# drone_V2.net
KiCad netlist of a schematic drawn in EAGLE
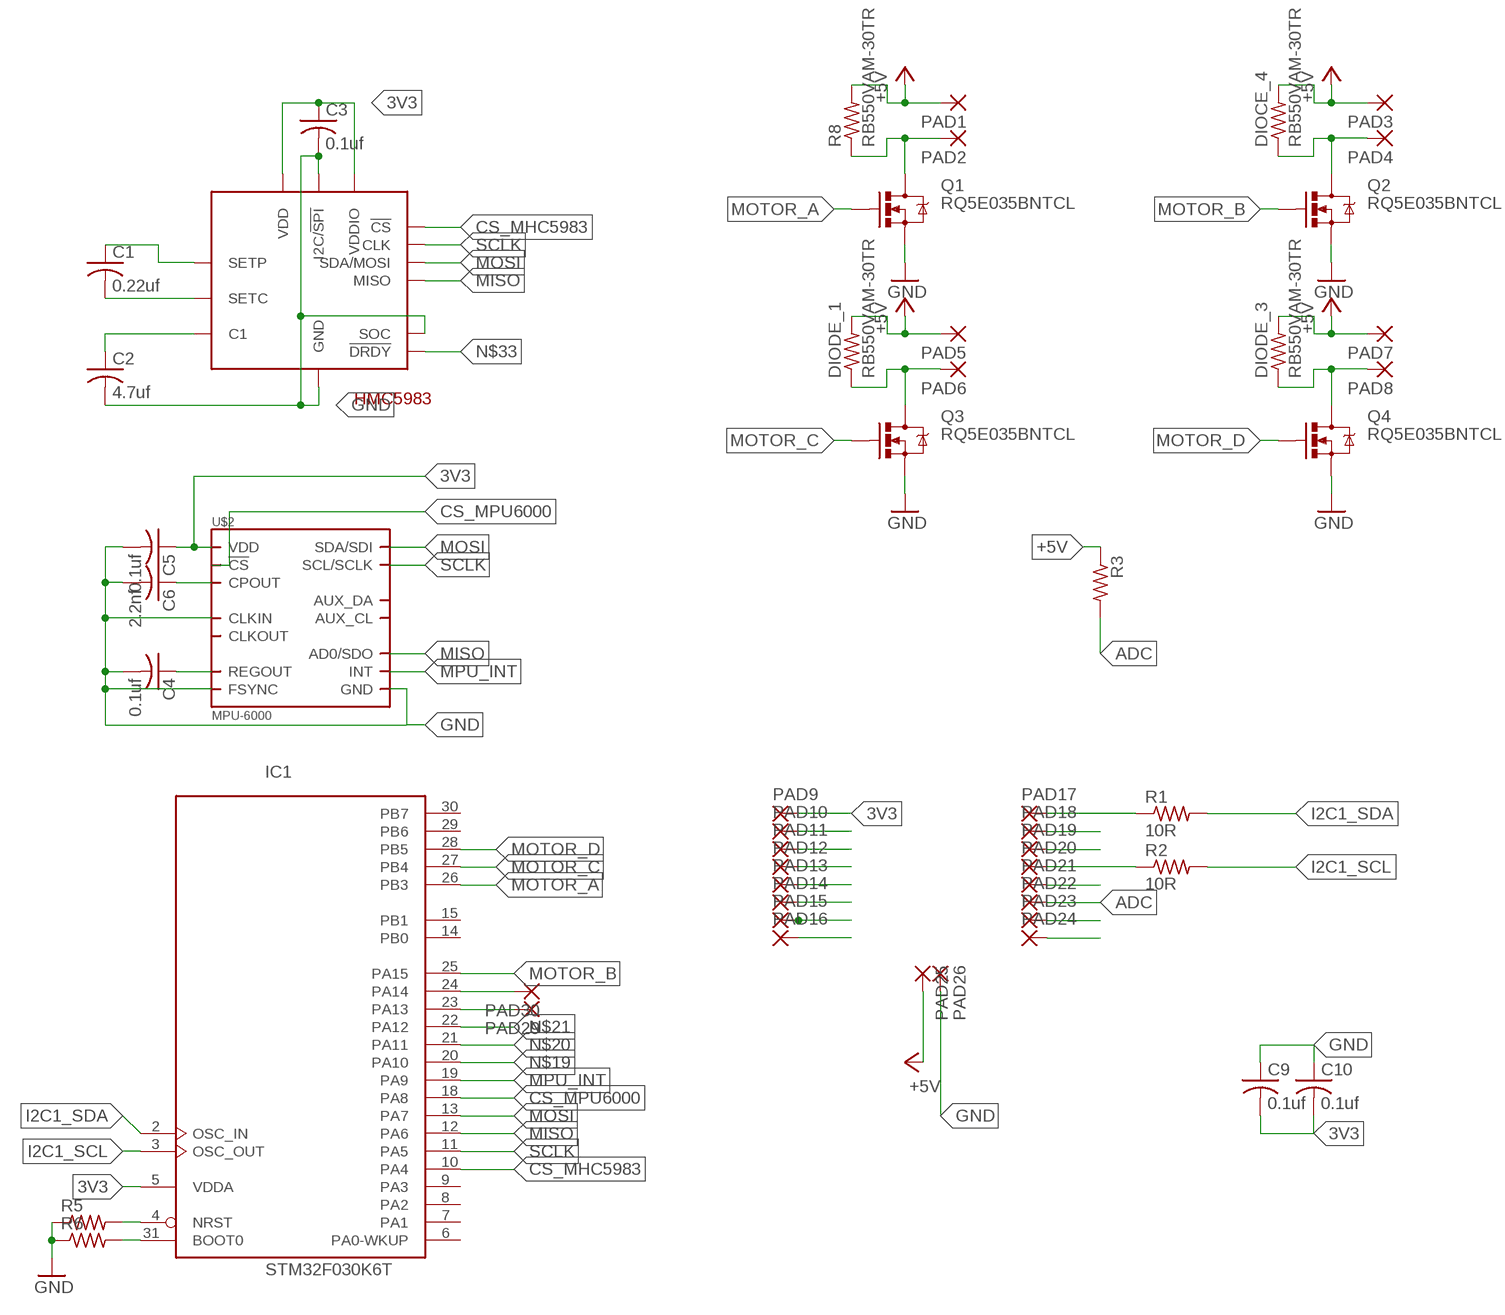
[diagram p0: schematic, sheet 1]

(export (version "E")
  (design (tool "Eeschema 10.0.6"))
  (components
    (comp (ref "C1")
      (value "0.22uf")
      (footprint "eagle-import:C0805K")
      (libsource (lib "eagle-import") (part "C-USC0805K"))
    )
    (comp (ref "C2")
      (value "4.7uf")
      (footprint "eagle-import:C1206")
      (libsource (lib "eagle-import") (part "C-USC1206"))
    )
    (comp (ref "C3")
      (value "0.1uf")
      (footprint "eagle-import:C0805K")
      (libsource (lib "eagle-import") (part "C-USC0805K"))
    )
    (comp (ref "C4")
      (value "0.1uf")
      (footprint "eagle-import:C0805K")
      (libsource (lib "eagle-import") (part "C-USC0805K"))
    )
    (comp (ref "C5")
      (value "0.1uf")
      (footprint "eagle-import:C0805K")
      (libsource (lib "eagle-import") (part "C-USC0805K"))
    )
    (comp (ref "C6")
      (value "2.2nf")
      (footprint "eagle-import:C0805K")
      (libsource (lib "eagle-import") (part "C-USC0805K"))
    )
    (comp (ref "C9")
      (value "0.1uf")
      (footprint "eagle-import:C0805K")
      (libsource (lib "eagle-import") (part "C-USC0805K"))
    )
    (comp (ref "C10")
      (value "0.1uf")
      (footprint "eagle-import:C0805K")
      (libsource (lib "eagle-import") (part "C-USC0805K"))
    )
    (comp (ref "DIOCE_4")
      (value "RB550VAM-30TR")
      (footprint "eagle-import:R0805")
      (libsource (lib "eagle-import") (part "R-US_R0805"))
    )
    (comp (ref "DIODE_1")
      (value "RB550VAM-30TR")
      (footprint "eagle-import:R0805")
      (libsource (lib "eagle-import") (part "R-US_R0805"))
    )
    (comp (ref "DIODE_3")
      (value "RB550VAM-30TR")
      (footprint "eagle-import:R0805")
      (libsource (lib "eagle-import") (part "R-US_R0805"))
    )
    (comp (ref "HMC5983")
      (value "HMC5983")
      (footprint "eagle-import:LPCC16")
      (libsource (lib "eagle-import") (part "HMC5983"))
    )
    (comp (ref "IC1")
      (value "STM32F030K6T")
      (footprint "eagle-import:LQFP32")
      (libsource (lib "eagle-import") (part "STM32F030KT6"))
    )
    (comp (ref "PAD1")
      (value "1,6/0,8")
      (footprint "eagle-import:1,6_0,8")
      (libsource (lib "eagle-import") (part "1,6/0,8"))
    )
    (comp (ref "PAD2")
      (value "1,6/0,8")
      (footprint "eagle-import:1,6_0,8")
      (libsource (lib "eagle-import") (part "1,6/0,8"))
    )
    (comp (ref "PAD3")
      (value "1,6/0,8")
      (footprint "eagle-import:1,6_0,8")
      (libsource (lib "eagle-import") (part "1,6/0,8"))
    )
    (comp (ref "PAD4")
      (value "1,6/0,8")
      (footprint "eagle-import:1,6_0,8")
      (libsource (lib "eagle-import") (part "1,6/0,8"))
    )
    (comp (ref "PAD5")
      (value "1,6/0,8")
      (footprint "eagle-import:1,6_0,8")
      (libsource (lib "eagle-import") (part "1,6/0,8"))
    )
    (comp (ref "PAD6")
      (value "1,6/0,8")
      (footprint "eagle-import:1,6_0,8")
      (libsource (lib "eagle-import") (part "1,6/0,8"))
    )
    (comp (ref "PAD7")
      (value "1,6/0,8")
      (footprint "eagle-import:1,6_0,8")
      (libsource (lib "eagle-import") (part "1,6/0,8"))
    )
    (comp (ref "PAD8")
      (value "1,6/0,8")
      (footprint "eagle-import:1,6_0,8")
      (libsource (lib "eagle-import") (part "1,6/0,8"))
    )
    (comp (ref "PAD9")
      (value "1,6/0,9")
      (footprint "eagle-import:1,6_0,9")
      (libsource (lib "eagle-import") (part "1,6/0,9"))
    )
    (comp (ref "PAD10")
      (value "1,6/0,9")
      (footprint "eagle-import:1,6_0,9")
      (libsource (lib "eagle-import") (part "1,6/0,9"))
    )
    (comp (ref "PAD11")
      (value "1,6/0,9")
      (footprint "eagle-import:1,6_0,9")
      (libsource (lib "eagle-import") (part "1,6/0,9"))
    )
    (comp (ref "PAD12")
      (value "1,6/0,9")
      (footprint "eagle-import:1,6_0,9")
      (libsource (lib "eagle-import") (part "1,6/0,9"))
    )
    (comp (ref "PAD13")
      (value "1,6/0,9")
      (footprint "eagle-import:1,6_0,9")
      (libsource (lib "eagle-import") (part "1,6/0,9"))
    )
    (comp (ref "PAD14")
      (value "1,6/0,9")
      (footprint "eagle-import:1,6_0,9")
      (libsource (lib "eagle-import") (part "1,6/0,9"))
    )
    (comp (ref "PAD15")
      (value "1,6/0,9")
      (footprint "eagle-import:1,6_0,9")
      (libsource (lib "eagle-import") (part "1,6/0,9"))
    )
    (comp (ref "PAD16")
      (value "1,6/0,9")
      (footprint "eagle-import:1,6_0,9")
      (libsource (lib "eagle-import") (part "1,6/0,9"))
    )
    (comp (ref "PAD17")
      (value "1,6/0,9")
      (footprint "eagle-import:1,6_0,9")
      (libsource (lib "eagle-import") (part "1,6/0,9"))
    )
    (comp (ref "PAD18")
      (value "1,6/0,9")
      (footprint "eagle-import:1,6_0,9")
      (libsource (lib "eagle-import") (part "1,6/0,9"))
    )
    (comp (ref "PAD19")
      (value "1,6/0,9")
      (footprint "eagle-import:1,6_0,9")
      (libsource (lib "eagle-import") (part "1,6/0,9"))
    )
    (comp (ref "PAD20")
      (value "1,6/0,9")
      (footprint "eagle-import:1,6_0,9")
      (libsource (lib "eagle-import") (part "1,6/0,9"))
    )
    (comp (ref "PAD21")
      (value "1,6/0,9")
      (footprint "eagle-import:1,6_0,9")
      (libsource (lib "eagle-import") (part "1,6/0,9"))
    )
    (comp (ref "PAD22")
      (value "1,6/0,9")
      (footprint "eagle-import:1,6_0,9")
      (libsource (lib "eagle-import") (part "1,6/0,9"))
    )
    (comp (ref "PAD23")
      (value "1,6/0,9")
      (footprint "eagle-import:1,6_0,9")
      (libsource (lib "eagle-import") (part "1,6/0,9"))
    )
    (comp (ref "PAD24")
      (value "1,6/0,9")
      (footprint "eagle-import:1,6_0,9")
      (libsource (lib "eagle-import") (part "1,6/0,9"))
    )
    (comp (ref "PAD25")
      (value "1,6/0,9")
      (footprint "eagle-import:1,6_0,9")
      (libsource (lib "eagle-import") (part "1,6/0,9"))
    )
    (comp (ref "PAD26")
      (value "1,6/0,9")
      (footprint "eagle-import:1,6_0,9")
      (libsource (lib "eagle-import") (part "1,6/0,9"))
    )
    (comp (ref "PAD29")
      (value "1,6/0,9")
      (footprint "eagle-import:1,6_0,9")
      (libsource (lib "eagle-import") (part "1,6/0,9"))
    )
    (comp (ref "PAD30")
      (value "1,6/0,9")
      (footprint "eagle-import:1,6_0,9")
      (libsource (lib "eagle-import") (part "1,6/0,9"))
    )
    (comp (ref "Q1")
      (value "RQ5E035BNTCL")
      (footprint "eagle-import:SOT23-3")
      (libsource (lib "eagle-import") (part "MOSFET-NCHANNELSMD"))
    )
    (comp (ref "Q2")
      (value "RQ5E035BNTCL")
      (footprint "eagle-import:SOT23-3")
      (libsource (lib "eagle-import") (part "MOSFET-NCHANNELSMD"))
    )
    (comp (ref "Q3")
      (value "RQ5E035BNTCL")
      (footprint "eagle-import:SOT23-3")
      (libsource (lib "eagle-import") (part "MOSFET-NCHANNELSMD"))
    )
    (comp (ref "Q4")
      (value "RQ5E035BNTCL")
      (footprint "eagle-import:SOT23-3")
      (libsource (lib "eagle-import") (part "MOSFET-NCHANNELSMD"))
    )
    (comp (ref "R1")
      (value "10R")
      (footprint "eagle-import:R0805")
      (libsource (lib "eagle-import") (part "resistor_R-US_R0805"))
    )
    (comp (ref "R2")
      (value "10R")
      (footprint "eagle-import:R0805")
      (libsource (lib "eagle-import") (part "resistor_R-US_R0805"))
    )
    (comp (ref "R3")
      (value "R-US_R0805")
      (footprint "eagle-import:R0805")
      (libsource (lib "eagle-import") (part "resistor_R-US_R0805"))
    )
    (comp (ref "R5")
      (value "R-US_R0805")
      (footprint "eagle-import:R0805")
      (libsource (lib "eagle-import") (part "resistor_R-US_R0805"))
    )
    (comp (ref "R6")
      (value "R-US_R0805")
      (footprint "eagle-import:R0805")
      (libsource (lib "eagle-import") (part "resistor_R-US_R0805"))
    )
    (comp (ref "R8")
      (value "RB550VAM-30TR")
      (footprint "eagle-import:R0805")
      (libsource (lib "eagle-import") (part "R-US_R0805"))
    )
    (comp (ref "U$2")
      (value "MPU-6000")
      (footprint "eagle-import:QFN.24.4X4")
      (libsource (lib "eagle-import") (part "MPU-6000"))
    )
  )
  (nets
    (net (code "1") (name "+5V") (class "Default")
      (node (ref "DIOCE_4") (pin "2") (pinfunction "2_2") (pintype "passive"))
      (node (ref "DIODE_1") (pin "2") (pinfunction "2_2") (pintype "passive"))
      (node (ref "DIODE_3") (pin "2") (pinfunction "2_2") (pintype "passive"))
      (node (ref "PAD1") (pin "1") (pinfunction "P_1") (pintype "passive"))
      (node (ref "PAD25") (pin "1") (pinfunction "P_1") (pintype "passive"))
      (node (ref "PAD3") (pin "1") (pinfunction "P_1") (pintype "passive"))
      (node (ref "PAD5") (pin "1") (pinfunction "P_1") (pintype "passive"))
      (node (ref "PAD7") (pin "1") (pinfunction "P_1") (pintype "passive"))
      (node (ref "R3") (pin "1") (pinfunction "1_1") (pintype "passive"))
      (node (ref "R8") (pin "2") (pinfunction "2_2") (pintype "passive"))
    )
    (net (code "2") (name "3V3") (class "Default")
      (node (ref "C10") (pin "2") (pinfunction "2_2") (pintype "passive"))
      (node (ref "C3") (pin "1") (pinfunction "1_1") (pintype "passive"))
      (node (ref "C5") (pin "1") (pinfunction "1_1") (pintype "passive"))
      (node (ref "C9") (pin "2") (pinfunction "2_2") (pintype "passive"))
      (node (ref "HMC5983") (pin "P$13") (pinfunction "VDDIO_P$13") (pintype "power_in"))
      (node (ref "HMC5983") (pin "P$2") (pinfunction "VDD_P$2") (pintype "power_in"))
      (node (ref "IC1") (pin "5") (pinfunction "VDDA_5") (pintype "power_in"))
      (node (ref "PAD9") (pin "1") (pinfunction "P_1") (pintype "passive"))
      (node (ref "U$2") (pin "13") (pinfunction "VDD_13") (pintype "bidirectional"))
    )
    (net (code "3") (name "ADC") (class "Default")
      (node (ref "PAD22") (pin "1") (pinfunction "P_1") (pintype "passive"))
      (node (ref "R3") (pin "2") (pinfunction "2_2") (pintype "passive"))
    )
    (net (code "4") (name "CS_MHC5983") (class "Default")
      (node (ref "HMC5983") (pin "P$4") (pinfunction "~{CS}_P$4") (pintype "input"))
      (node (ref "IC1") (pin "10") (pinfunction "PA4_10") (pintype "bidirectional"))
    )
    (net (code "5") (name "CS_MPU6000") (class "Default")
      (node (ref "IC1") (pin "18") (pinfunction "PA8_18") (pintype "bidirectional"))
      (node (ref "U$2") (pin "8") (pinfunction "~{CS}_8") (pintype "bidirectional"))
    )
    (net (code "6") (name "GND") (class "Default")
      (node (ref "C10") (pin "1") (pinfunction "1_1") (pintype "passive"))
      (node (ref "C2") (pin "2") (pinfunction "2_2") (pintype "passive"))
      (node (ref "C3") (pin "2") (pinfunction "2_2") (pintype "passive"))
      (node (ref "C4") (pin "2") (pinfunction "2_2") (pintype "passive"))
      (node (ref "C5") (pin "2") (pinfunction "2_2") (pintype "passive"))
      (node (ref "C6") (pin "2") (pinfunction "2_2") (pintype "passive"))
      (node (ref "C9") (pin "1") (pinfunction "1_1") (pintype "passive"))
      (node (ref "HMC5983") (pin "P$11") (pinfunction "GND_P$11") (pintype "power_in"))
      (node (ref "HMC5983") (pin "P$6") (pinfunction "I2C/~{SPI}_P$6") (pintype "input"))
      (node (ref "HMC5983") (pin "P$9") (pinfunction "SOC_P$9") (pintype "input"))
      (node (ref "PAD24") (pin "1") (pinfunction "P_1") (pintype "passive"))
      (node (ref "PAD26") (pin "1") (pinfunction "P_1") (pintype "passive"))
      (node (ref "Q1") (pin "2") (pinfunction "S_2") (pintype "passive"))
      (node (ref "Q2") (pin "2") (pinfunction "S_2") (pintype "passive"))
      (node (ref "Q3") (pin "2") (pinfunction "S_2") (pintype "passive"))
      (node (ref "Q4") (pin "2") (pinfunction "S_2") (pintype "passive"))
      (node (ref "R5") (pin "1") (pinfunction "1_1") (pintype "passive"))
      (node (ref "R6") (pin "1") (pinfunction "1_1") (pintype "passive"))
      (node (ref "U$2") (pin "1") (pinfunction "CLKIN_1") (pintype "bidirectional"))
      (node (ref "U$2") (pin "11") (pinfunction "FSYNC_11") (pintype "bidirectional"))
      (node (ref "U$2") (pin "18") (pinfunction "GND_18") (pintype "bidirectional"))
    )
    (net (code "7") (name "I2C1_SCL") (class "Default")
      (node (ref "IC1") (pin "3") (pinfunction "OSC_OUT_3") (pintype "bidirectional"))
      (node (ref "R2") (pin "2") (pinfunction "2_2") (pintype "passive"))
    )
    (net (code "8") (name "I2C1_SDA") (class "Default")
      (node (ref "IC1") (pin "2") (pinfunction "OSC_IN_2") (pintype "bidirectional"))
      (node (ref "R1") (pin "2") (pinfunction "2_2") (pintype "passive"))
    )
    (net (code "9") (name "MISO") (class "Default")
      (node (ref "HMC5983") (pin "P$5") (pinfunction "MISO_P$5") (pintype "output"))
      (node (ref "IC1") (pin "12") (pinfunction "PA6_12") (pintype "bidirectional"))
      (node (ref "U$2") (pin "9") (pinfunction "AD0/SDO_9") (pintype "bidirectional"))
    )
    (net (code "10") (name "MOSI") (class "Default")
      (node (ref "HMC5983") (pin "P$16") (pinfunction "SDA/MOSI_P$16") (pintype "input"))
      (node (ref "IC1") (pin "13") (pinfunction "PA7_13") (pintype "bidirectional"))
      (node (ref "U$2") (pin "24") (pinfunction "SDA/SDI_24") (pintype "bidirectional"))
    )
    (net (code "11") (name "MOTOR_A") (class "Default")
      (node (ref "IC1") (pin "26") (pinfunction "PB3_26") (pintype "bidirectional"))
      (node (ref "Q1") (pin "1") (pinfunction "G_1") (pintype "passive"))
    )
    (net (code "12") (name "MOTOR_B") (class "Default")
      (node (ref "IC1") (pin "25") (pinfunction "PA15_25") (pintype "bidirectional"))
      (node (ref "Q2") (pin "1") (pinfunction "G_1") (pintype "passive"))
    )
    (net (code "13") (name "MOTOR_C") (class "Default")
      (node (ref "IC1") (pin "27") (pinfunction "PB4_27") (pintype "bidirectional"))
      (node (ref "Q3") (pin "1") (pinfunction "G_1") (pintype "passive"))
    )
    (net (code "14") (name "MOTOR_D") (class "Default")
      (node (ref "IC1") (pin "28") (pinfunction "PB5_28") (pintype "bidirectional"))
      (node (ref "Q4") (pin "1") (pinfunction "G_1") (pintype "passive"))
    )
    (net (code "15") (name "MPU_INT") (class "Default")
      (node (ref "IC1") (pin "19") (pinfunction "PA9_19") (pintype "bidirectional"))
      (node (ref "U$2") (pin "12") (pinfunction "INT_12") (pintype "bidirectional"))
    )
    (net (code "16") (name "N$19") (class "Default")
      (node (ref "IC1") (pin "20") (pinfunction "PA10_20") (pintype "bidirectional"))
    )
    (net (code "17") (name "N$20") (class "Default")
      (node (ref "IC1") (pin "21") (pinfunction "PA11_21") (pintype "bidirectional"))
    )
    (net (code "18") (name "N$21") (class "Default")
      (node (ref "IC1") (pin "22") (pinfunction "PA12_22") (pintype "bidirectional"))
    )
    (net (code "19") (name "N$33") (class "Default")
      (node (ref "HMC5983") (pin "P$15") (pinfunction "~{DRDY}_P$15") (pintype "output"))
    )
    (net (code "20") (name "Net-(HMC5983-C1)") (class "Default")
      (node (ref "C2") (pin "1") (pinfunction "1_1") (pintype "passive"))
      (node (ref "HMC5983") (pin "P$10") (pinfunction "C1_P$10") (pintype "passive"))
    )
    (net (code "21") (name "Net-(HMC5983-SETC)") (class "Default")
      (node (ref "C1") (pin "2") (pinfunction "2_2") (pintype "passive"))
      (node (ref "HMC5983") (pin "P$12") (pinfunction "SETC_P$12") (pintype "passive"))
    )
    (net (code "22") (name "Net-(HMC5983-SETP)") (class "Default")
      (node (ref "C1") (pin "1") (pinfunction "1_1") (pintype "passive"))
      (node (ref "HMC5983") (pin "P$8") (pinfunction "SETP_P$8") (pintype "passive"))
    )
    (net (code "23") (name "Net-(IC1A-BOOT0)") (class "Default")
      (node (ref "IC1") (pin "31") (pinfunction "BOOT0_31") (pintype "input"))
      (node (ref "R6") (pin "2") (pinfunction "2_2") (pintype "passive"))
    )
    (net (code "24") (name "Net-(IC1A-NRST)") (class "Default")
      (node (ref "IC1") (pin "4") (pinfunction "NRST_4") (pintype "bidirectional"))
      (node (ref "R5") (pin "2") (pinfunction "2_2") (pintype "passive"))
    )
    (net (code "25") (name "Net-(IC1A-PA13)") (class "Default")
      (node (ref "IC1") (pin "23") (pinfunction "PA13_23") (pintype "bidirectional"))
      (node (ref "PAD29") (pin "1") (pinfunction "P_1") (pintype "passive"))
    )
    (net (code "26") (name "Net-(IC1A-PA14)") (class "Default")
      (node (ref "IC1") (pin "24") (pinfunction "PA14_24") (pintype "bidirectional"))
      (node (ref "PAD30") (pin "1") (pinfunction "P_1") (pintype "passive"))
    )
    (net (code "27") (name "Net-(PAD2-P)") (class "Default")
      (node (ref "PAD2") (pin "1") (pinfunction "P_1") (pintype "passive"))
      (node (ref "Q1") (pin "3") (pinfunction "D_3") (pintype "passive"))
      (node (ref "R8") (pin "1") (pinfunction "1_1") (pintype "passive"))
    )
    (net (code "28") (name "Net-(PAD4-P)") (class "Default")
      (node (ref "DIOCE_4") (pin "1") (pinfunction "1_1") (pintype "passive"))
      (node (ref "PAD4") (pin "1") (pinfunction "P_1") (pintype "passive"))
      (node (ref "Q2") (pin "3") (pinfunction "D_3") (pintype "passive"))
    )
    (net (code "29") (name "Net-(PAD6-P)") (class "Default")
      (node (ref "DIODE_1") (pin "1") (pinfunction "1_1") (pintype "passive"))
      (node (ref "PAD6") (pin "1") (pinfunction "P_1") (pintype "passive"))
      (node (ref "Q3") (pin "3") (pinfunction "D_3") (pintype "passive"))
    )
    (net (code "30") (name "Net-(PAD8-P)") (class "Default")
      (node (ref "DIODE_3") (pin "1") (pinfunction "1_1") (pintype "passive"))
      (node (ref "PAD8") (pin "1") (pinfunction "P_1") (pintype "passive"))
      (node (ref "Q4") (pin "3") (pinfunction "D_3") (pintype "passive"))
    )
    (net (code "31") (name "Net-(PAD17-P)") (class "Default")
      (node (ref "PAD17") (pin "1") (pinfunction "P_1") (pintype "passive"))
      (node (ref "R1") (pin "1") (pinfunction "1_1") (pintype "passive"))
    )
    (net (code "32") (name "Net-(PAD20-P)") (class "Default")
      (node (ref "PAD20") (pin "1") (pinfunction "P_1") (pintype "passive"))
      (node (ref "R2") (pin "1") (pinfunction "1_1") (pintype "passive"))
    )
    (net (code "33") (name "Net-(U$2-CPOUT)") (class "Default")
      (node (ref "C6") (pin "1") (pinfunction "1_1") (pintype "passive"))
      (node (ref "U$2") (pin "20") (pinfunction "CPOUT_20") (pintype "bidirectional"))
    )
    (net (code "34") (name "Net-(U$2-REGOUT)") (class "Default")
      (node (ref "C4") (pin "1") (pinfunction "1_1") (pintype "passive"))
      (node (ref "U$2") (pin "10") (pinfunction "REGOUT_10") (pintype "bidirectional"))
    )
    (net (code "35") (name "SCLK") (class "Default")
      (node (ref "HMC5983") (pin "P$1") (pinfunction "CLK_P$1") (pintype "input"))
      (node (ref "IC1") (pin "11") (pinfunction "PA5_11") (pintype "bidirectional"))
      (node (ref "U$2") (pin "23") (pinfunction "SCL/SCLK_23") (pintype "bidirectional"))
    )
    (net (code "36") (name "unconnected-(IC1A-PA0-WKUP-Pad6)") (class "Default")
      (node (ref "IC1") (pin "6") (pinfunction "PA0-WKUP_6") (pintype "bidirectional"))
    )
    (net (code "37") (name "unconnected-(IC1A-PA1-Pad7)") (class "Default")
      (node (ref "IC1") (pin "7") (pinfunction "PA1_7") (pintype "bidirectional"))
    )
    (net (code "38") (name "unconnected-(IC1A-PA2-Pad8)") (class "Default")
      (node (ref "IC1") (pin "8") (pinfunction "PA2_8") (pintype "bidirectional"))
    )
    (net (code "39") (name "unconnected-(IC1A-PA3-Pad9)") (class "Default")
      (node (ref "IC1") (pin "9") (pinfunction "PA3_9") (pintype "bidirectional"))
    )
    (net (code "40") (name "unconnected-(IC1A-PB0-Pad14)") (class "Default")
      (node (ref "IC1") (pin "14") (pinfunction "PB0_14") (pintype "bidirectional"))
    )
    (net (code "41") (name "unconnected-(IC1A-PB1-Pad15)") (class "Default")
      (node (ref "IC1") (pin "15") (pinfunction "PB1_15") (pintype "bidirectional"))
    )
    (net (code "42") (name "unconnected-(IC1A-PB6-Pad29)") (class "Default")
      (node (ref "IC1") (pin "29") (pinfunction "PB6_29") (pintype "bidirectional"))
    )
    (net (code "43") (name "unconnected-(IC1A-PB7-Pad30)") (class "Default")
      (node (ref "IC1") (pin "30") (pinfunction "PB7_30") (pintype "bidirectional"))
    )
    (net (code "44") (name "unconnected-(PAD10-P-Pad1)") (class "Default")
      (node (ref "PAD10") (pin "1") (pinfunction "P_1") (pintype "passive"))
    )
    (net (code "45") (name "unconnected-(PAD11-P-Pad1)") (class "Default")
      (node (ref "PAD11") (pin "1") (pinfunction "P_1") (pintype "passive"))
    )
    (net (code "46") (name "unconnected-(PAD12-P-Pad1)") (class "Default")
      (node (ref "PAD12") (pin "1") (pinfunction "P_1") (pintype "passive"))
    )
    (net (code "47") (name "unconnected-(PAD13-P-Pad1)") (class "Default")
      (node (ref "PAD13") (pin "1") (pinfunction "P_1") (pintype "passive"))
    )
    (net (code "48") (name "unconnected-(PAD14-P-Pad1)") (class "Default")
      (node (ref "PAD14") (pin "1") (pinfunction "P_1") (pintype "passive"))
    )
    (net (code "49") (name "unconnected-(PAD15-P-Pad1)") (class "Default")
      (node (ref "PAD15") (pin "1") (pinfunction "P_1") (pintype "passive"))
    )
    (net (code "50") (name "unconnected-(PAD16-P-Pad1)") (class "Default")
      (node (ref "PAD16") (pin "1") (pinfunction "P_1") (pintype "passive"))
    )
    (net (code "51") (name "unconnected-(PAD18-P-Pad1)") (class "Default")
      (node (ref "PAD18") (pin "1") (pinfunction "P_1") (pintype "passive"))
    )
    (net (code "52") (name "unconnected-(PAD19-P-Pad1)") (class "Default")
      (node (ref "PAD19") (pin "1") (pinfunction "P_1") (pintype "passive"))
    )
    (net (code "53") (name "unconnected-(PAD21-P-Pad1)") (class "Default")
      (node (ref "PAD21") (pin "1") (pinfunction "P_1") (pintype "passive"))
    )
    (net (code "54") (name "unconnected-(PAD23-P-Pad1)") (class "Default")
      (node (ref "PAD23") (pin "1") (pinfunction "P_1") (pintype "passive"))
    )
    (net (code "55") (name "unconnected-(U$2-AUX_CL-Pad7)") (class "Default")
      (node (ref "U$2") (pin "7") (pinfunction "AUX_CL_7") (pintype "bidirectional"))
    )
    (net (code "56") (name "unconnected-(U$2-AUX_DA-Pad6)") (class "Default")
      (node (ref "U$2") (pin "6") (pinfunction "AUX_DA_6") (pintype "bidirectional"))
    )
    (net (code "57") (name "unconnected-(U$2-CLKOUT-Pad22)") (class "Default")
      (node (ref "U$2") (pin "22") (pinfunction "CLKOUT_22") (pintype "bidirectional"))
    )
  )
)
